# Motor0.net
KiCad netlist of a schematic drawn in Altium Designer
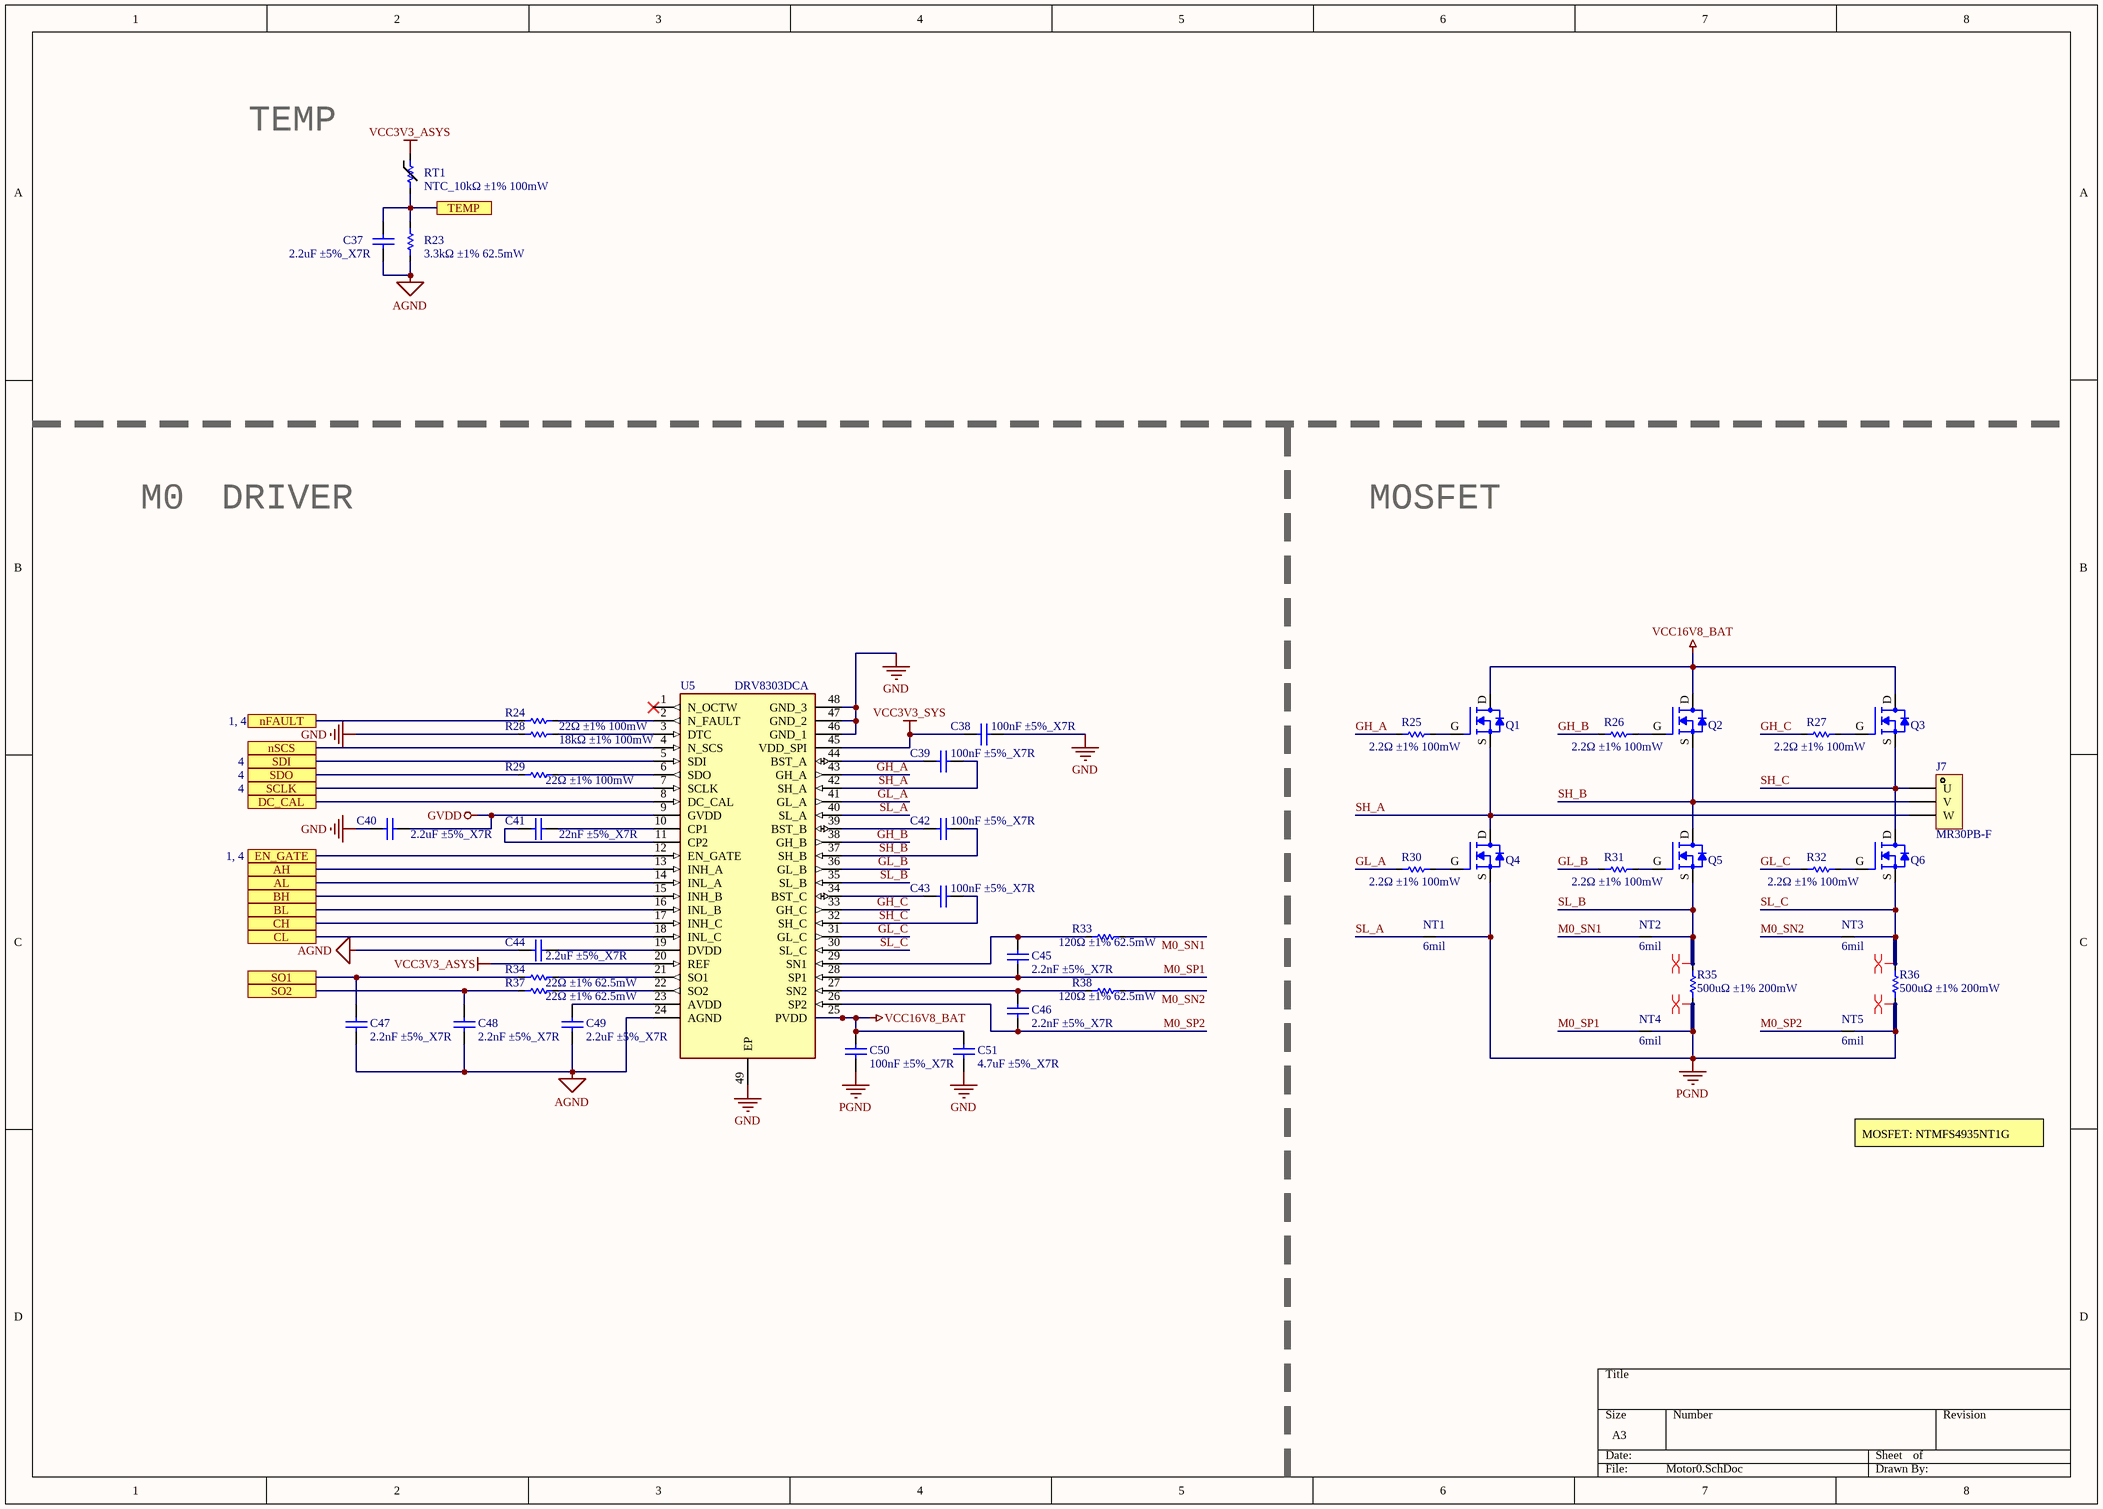
[diagram p0: Motor0.SchDoc]

(export (version "E")
  (design (tool "Eeschema 10.0.6"))
  (components
    (comp (ref "C37")
      (value "2.2uF ±5%_X7R")
      (footprint "C0402")
      (description "Capacitor")
      (fields (field (name "PUBLISHER") "Altium Limited"))
      (libsource (lib "Component") (part "Cap"))
    )
    (comp (ref "C38")
      (value "100nF ±5%_X7R")
      (footprint "C0402")
      (description "Capacitor")
      (fields (field (name "PUBLISHER") "Altium Limited"))
      (libsource (lib "Component") (part "Cap"))
    )
    (comp (ref "C39")
      (value "100nF ±5%_X7R")
      (footprint "C0402")
      (description "Capacitor")
      (fields (field (name "PUBLISHER") "Altium Limited"))
      (libsource (lib "Component") (part "Cap"))
    )
    (comp (ref "C40")
      (value "2.2uF ±5%_X7R")
      (footprint "C0402")
      (description "CL05A225KO5NQNC")
      (fields (field (name "PUBLISHER") "Altium Limited"))
      (libsource (lib "Component") (part "Cap"))
    )
    (comp (ref "C41")
      (value "22nF ±5%_X7R")
      (footprint "C0402")
      (description "Capacitor")
      (fields (field (name "PUBLISHER") "Altium Limited"))
      (libsource (lib "Component") (part "Cap"))
    )
    (comp (ref "C42")
      (value "100nF ±5%_X7R")
      (footprint "C0402")
      (description "Capacitor")
      (fields (field (name "PUBLISHER") "Altium Limited"))
      (libsource (lib "Component") (part "Cap"))
    )
    (comp (ref "C43")
      (value "100nF ±5%_X7R")
      (footprint "C0402")
      (description "Capacitor")
      (fields (field (name "PUBLISHER") "Altium Limited"))
      (libsource (lib "Component") (part "Cap"))
    )
    (comp (ref "C44")
      (value "2.2uF ±5%_X7R")
      (footprint "C0402")
      (description "CL05A225KO5NQNC")
      (fields (field (name "PUBLISHER") "Altium Limited"))
      (libsource (lib "Component") (part "Cap"))
    )
    (comp (ref "C45")
      (value "2.2nF ±5%_X7R")
      (footprint "C0402")
      (description "Capacitor")
      (fields (field (name "PUBLISHER") "Altium Limited"))
      (libsource (lib "Component") (part "Cap"))
    )
    (comp (ref "C46")
      (value "2.2nF ±5%_X7R")
      (footprint "C0402")
      (description "Capacitor")
      (fields (field (name "PUBLISHER") "Altium Limited"))
      (libsource (lib "Component") (part "Cap"))
    )
    (comp (ref "C47")
      (value "2.2nF ±5%_X7R")
      (footprint "C0402")
      (description "Capacitor")
      (fields (field (name "PUBLISHER") "Altium Limited"))
      (libsource (lib "Component") (part "Cap"))
    )
    (comp (ref "C48")
      (value "2.2nF ±5%_X7R")
      (footprint "C0402")
      (description "Capacitor")
      (fields (field (name "PUBLISHER") "Altium Limited"))
      (libsource (lib "Component") (part "Cap"))
    )
    (comp (ref "C49")
      (value "2.2uF ±5%_X7R")
      (footprint "C0402")
      (description "CL05A225KO5NQNC")
      (fields (field (name "PUBLISHER") "Altium Limited"))
      (libsource (lib "Component") (part "Cap"))
    )
    (comp (ref "C50")
      (value "100nF ±5%_X7R")
      (footprint "C0402")
      (description "Capacitor")
      (fields (field (name "PUBLISHER") "Altium Limited"))
      (libsource (lib "Component") (part "Cap"))
    )
    (comp (ref "C51")
      (value "4.7uF ±5%_X7R")
      (footprint "C0603")
      (description "Capacitor")
      (fields (field (name "PUBLISHER") "Altium Limited"))
      (libsource (lib "Component") (part "Cap"))
    )
    (comp (ref "J7")
      (value "MR30PB-F")
      (footprint "MR30PB-F [Straight] [SMT]")
      (description "驱动器端")
      (libsource (lib "Connectivity_Plugs") (part "MR30PB-F [Straight] [SMT]"))
    )
    (comp (ref "NT1") (value "6mil") (footprint "NETTIE_6mil") (libsource (lib "Component") (part "NETTIE")))
    (comp (ref "NT2") (value "6mil") (footprint "NETTIE_6mil") (libsource (lib "Component") (part "NETTIE")))
    (comp (ref "NT3") (value "6mil") (footprint "NETTIE_6mil") (libsource (lib "Component") (part "NETTIE")))
    (comp (ref "NT4") (value "6mil") (footprint "NETTIE_6mil") (libsource (lib "Component") (part "NETTIE")))
    (comp (ref "NT5") (value "6mil") (footprint "NETTIE_6mil") (libsource (lib "Component") (part "NETTIE")))
    (comp (ref "Q1")
      (value "BSC027N04LSG")
      (footprint "NRVTS10100EMFST1G")
      (description "MOSFET – Power, Single,\r\nN-Channel, PG-TDSON-8\r\nSuperSO8 5x6\r\n40 V, 139 A")
      (fields
        (field (name "MANUFACTURER") "ON Semiconductor")
        (field (name "MANUFACTURER PART NUMBER") "NTMFS4935NT1G")
      )
      (libsource (lib "Component") (part "MOSFET-N"))
    )
    (comp (ref "Q2")
      (value "BSC027N04LSG")
      (footprint "NRVTS10100EMFST1G")
      (description "MOSFET – Power, Single,\r\nN-Channel, PG-TDSON-8\r\nSuperSO8 5x6\r\n40 V, 139 A")
      (fields
        (field (name "MANUFACTURER") "ON Semiconductor")
        (field (name "MANUFACTURER PART NUMBER") "NTMFS4935NT1G")
      )
      (libsource (lib "Component") (part "MOSFET-N"))
    )
    (comp (ref "Q3")
      (value "BSC027N04LSG")
      (footprint "NRVTS10100EMFST1G")
      (description "MOSFET – Power, Single,\r\nN-Channel, PG-TDSON-8\r\nSuperSO8 5x6\r\n40 V, 139 A")
      (fields
        (field (name "MANUFACTURER") "ON Semiconductor")
        (field (name "MANUFACTURER PART NUMBER") "NTMFS4935NT1G")
      )
      (libsource (lib "Component") (part "MOSFET-N"))
    )
    (comp (ref "Q4")
      (value "BSC027N04LSG")
      (footprint "NRVTS10100EMFST1G")
      (description "MOSFET – Power, Single,\r\nN-Channel, PG-TDSON-8\r\nSuperSO8 5x6\r\n40 V, 139 A")
      (fields
        (field (name "MANUFACTURER") "ON Semiconductor")
        (field (name "MANUFACTURER PART NUMBER") "NTMFS4935NT1G")
      )
      (libsource (lib "Component") (part "MOSFET-N"))
    )
    (comp (ref "Q5")
      (value "BSC027N04LSG")
      (footprint "NRVTS10100EMFST1G")
      (description "MOSFET – Power, Single,\r\nN-Channel, PG-TDSON-8\r\nSuperSO8 5x6\r\n40 V, 139 A")
      (fields
        (field (name "MANUFACTURER") "ON Semiconductor")
        (field (name "MANUFACTURER PART NUMBER") "NTMFS4935NT1G")
      )
      (libsource (lib "Component") (part "MOSFET-N"))
    )
    (comp (ref "Q6")
      (value "BSC027N04LSG")
      (footprint "NRVTS10100EMFST1G")
      (description "MOSFET – Power, Single,\r\nN-Channel, PG-TDSON-8\r\nSuperSO8 5x6\r\n40 V, 139 A")
      (fields
        (field (name "MANUFACTURER") "ON Semiconductor")
        (field (name "MANUFACTURER PART NUMBER") "NTMFS4935NT1G")
      )
      (libsource (lib "Component") (part "MOSFET-N"))
    )
    (comp (ref "R23")
      (value "3.3kΩ ±1% 62.5mW")
      (footprint "R0402")
      (description "Resistor")
      (fields (field (name "PUBLISHER") "Altium Limited"))
      (libsource (lib "Component") (part "Res"))
    )
    (comp (ref "R24")
      (value "22Ω ±1% 100mW")
      (footprint "R0402")
      (description "Resistor")
      (fields (field (name "PUBLISHER") "Altium Limited"))
      (libsource (lib "Component") (part "Res"))
    )
    (comp (ref "R25")
      (value "2.2Ω ±1% 100mW")
      (footprint "R0402")
      (description "Resistor")
      (fields (field (name "PUBLISHER") "Altium Limited"))
      (libsource (lib "Component") (part "Res"))
    )
    (comp (ref "R26")
      (value "2.2Ω ±1% 100mW")
      (footprint "R0402")
      (description "Resistor")
      (fields (field (name "PUBLISHER") "Altium Limited"))
      (libsource (lib "Component") (part "Res"))
    )
    (comp (ref "R27")
      (value "2.2Ω ±1% 100mW")
      (footprint "R0402")
      (description "Resistor")
      (fields (field (name "PUBLISHER") "Altium Limited"))
      (libsource (lib "Component") (part "Res"))
    )
    (comp (ref "R28")
      (value "18kΩ ±1% 100mW")
      (footprint "R0402")
      (description "Resistor")
      (fields (field (name "PUBLISHER") "Altium Limited"))
      (libsource (lib "Component") (part "Res"))
    )
    (comp (ref "R29")
      (value "22Ω ±1% 100mW")
      (footprint "R0402")
      (description "Resistor")
      (fields (field (name "PUBLISHER") "Altium Limited"))
      (libsource (lib "Component") (part "Res"))
    )
    (comp (ref "R30")
      (value "2.2Ω ±1% 100mW")
      (footprint "R0402")
      (description "Resistor")
      (fields (field (name "PUBLISHER") "Altium Limited"))
      (libsource (lib "Component") (part "Res"))
    )
    (comp (ref "R31")
      (value "2.2Ω ±1% 100mW")
      (footprint "R0402")
      (description "Resistor")
      (fields (field (name "PUBLISHER") "Altium Limited"))
      (libsource (lib "Component") (part "Res"))
    )
    (comp (ref "R32")
      (value "2.2Ω ±1% 100mW")
      (footprint "R0402")
      (description "Resistor")
      (fields (field (name "PUBLISHER") "Altium Limited"))
      (libsource (lib "Component") (part "Res"))
    )
    (comp (ref "R33")
      (value "120Ω ±1% 62.5mW")
      (footprint "R0402")
      (description "Resistor")
      (fields (field (name "PUBLISHER") "Altium Limited"))
      (libsource (lib "Component") (part "Res"))
    )
    (comp (ref "R34")
      (value "22Ω ±1% 62.5mW")
      (footprint "R0402")
      (description "Resistor")
      (fields (field (name "PUBLISHER") "Altium Limited"))
      (libsource (lib "Component") (part "Res"))
    )
    (comp (ref "R35")
      (value "500uΩ ±1% 200mW")
      (footprint "R2512")
      (description "Resistor")
      (fields (field (name "PUBLISHER") "Altium Limited"))
      (libsource (lib "Component") (part "Res"))
    )
    (comp (ref "R36")
      (value "500uΩ ±1% 200mW")
      (footprint "R2512")
      (description "Resistor")
      (fields (field (name "PUBLISHER") "Altium Limited"))
      (libsource (lib "Component") (part "Res"))
    )
    (comp (ref "R37")
      (value "22Ω ±1% 62.5mW")
      (footprint "R0402")
      (description "Resistor")
      (fields (field (name "PUBLISHER") "Altium Limited"))
      (libsource (lib "Component") (part "Res"))
    )
    (comp (ref "R38")
      (value "120Ω ±1% 62.5mW")
      (footprint "R0402")
      (description "Resistor")
      (fields (field (name "PUBLISHER") "Altium Limited"))
      (libsource (lib "Component") (part "Res"))
    )
    (comp (ref "RT1")
      (value "NTC_10kΩ ±1% 100mW")
      (footprint "R0402")
      (description "THERMISTOR 10K OHM NTC 0402 SMD")
      (libsource (lib "Component") (part "TEMP RES"))
    )
    (comp (ref "U5")
      (value "DRV8303DCA")
      (footprint "SamacSys:SOP50P810X120-49N")
      (description "Integrated Circuit")
      (fields (field (name "MOUSER PART NUMBER") "595-DRV8303DCA"))
      (libsource (lib "*") (part "DRV8303DCA"))
    )
  )
  (nets
    (net (code "1") (name "/AH") (class "Default")
      (node (ref "U5") (pin "13") (pinfunction "INH_A_13") (pintype "input"))
    )
    (net (code "2") (name "/AL") (class "Default")
      (node (ref "U5") (pin "14") (pinfunction "INL_A_14") (pintype "input"))
    )
    (net (code "3") (name "/BH") (class "Default")
      (node (ref "U5") (pin "15") (pinfunction "INH_B_15") (pintype "input"))
    )
    (net (code "4") (name "/BL") (class "Default")
      (node (ref "U5") (pin "16") (pinfunction "INL_B_16") (pintype "input"))
    )
    (net (code "5") (name "/CH") (class "Default")
      (node (ref "U5") (pin "17") (pinfunction "INH_C_17") (pintype "input"))
    )
    (net (code "6") (name "/CL") (class "Default")
      (node (ref "U5") (pin "18") (pinfunction "INL_C_18") (pintype "input"))
    )
    (net (code "7") (name "/DC_CAL") (class "Default")
      (node (ref "U5") (pin "8") (pinfunction "DC_CAL_8") (pintype "input"))
    )
    (net (code "8") (name "/EN_GATE") (class "Default")
      (node (ref "U5") (pin "12") (pinfunction "EN_GATE_12") (pintype "input"))
    )
    (net (code "9") (name "/GH_A") (class "Default")
      (node (ref "R25") (pin "1") (pinfunction "1_1") (pintype "passive"))
      (node (ref "U5") (pin "43") (pinfunction "GH_A_43") (pintype "output"))
    )
    (net (code "10") (name "/GH_B") (class "Default")
      (node (ref "R26") (pin "1") (pinfunction "1_1") (pintype "passive"))
      (node (ref "U5") (pin "38") (pinfunction "GH_B_38") (pintype "output"))
    )
    (net (code "11") (name "/GH_C") (class "Default")
      (node (ref "R27") (pin "1") (pinfunction "1_1") (pintype "passive"))
      (node (ref "U5") (pin "33") (pinfunction "GH_C_33") (pintype "output"))
    )
    (net (code "12") (name "/GL_A") (class "Default")
      (node (ref "R30") (pin "1") (pinfunction "1_1") (pintype "passive"))
      (node (ref "U5") (pin "41") (pinfunction "GL_A_41") (pintype "output"))
    )
    (net (code "13") (name "/GL_B") (class "Default")
      (node (ref "R31") (pin "1") (pinfunction "1_1") (pintype "passive"))
      (node (ref "U5") (pin "36") (pinfunction "GL_B_36") (pintype "output"))
    )
    (net (code "14") (name "/GL_C") (class "Default")
      (node (ref "R32") (pin "1") (pinfunction "1_1") (pintype "passive"))
      (node (ref "U5") (pin "31") (pinfunction "GL_C_31") (pintype "output"))
    )
    (net (code "15") (name "/M0_SN1") (class "Default")
      (node (ref "NT2") (pin "1") (pinfunction "1_1") (pintype "passive"))
      (node (ref "R33") (pin "1") (pinfunction "1_1") (pintype "passive"))
    )
    (net (code "16") (name "/M0_SN2") (class "Default")
      (node (ref "NT3") (pin "1") (pinfunction "1_1") (pintype "passive"))
      (node (ref "R38") (pin "1") (pinfunction "1_1") (pintype "passive"))
    )
    (net (code "17") (name "/M0_SP1") (class "Default")
      (node (ref "C45") (pin "1") (pinfunction "1_1") (pintype "passive"))
      (node (ref "NT4") (pin "1") (pinfunction "1_1") (pintype "passive"))
      (node (ref "U5") (pin "28") (pinfunction "SP1_28") (pintype "input"))
    )
    (net (code "18") (name "/M0_SP2") (class "Default")
      (node (ref "C46") (pin "1") (pinfunction "1_1") (pintype "passive"))
      (node (ref "NT5") (pin "1") (pinfunction "1_1") (pintype "passive"))
      (node (ref "U5") (pin "26") (pinfunction "SP2_26") (pintype "input"))
    )
    (net (code "19") (name "/SCLK") (class "Default")
      (node (ref "U5") (pin "7") (pinfunction "SCLK_7") (pintype "input"))
    )
    (net (code "20") (name "/SDI") (class "Default")
      (node (ref "U5") (pin "5") (pinfunction "SDI_5") (pintype "input"))
    )
    (net (code "21") (name "/SDO") (class "Default")
      (node (ref "R29") (pin "1") (pinfunction "1_1") (pintype "passive"))
    )
    (net (code "22") (name "/SH_A") (class "Default")
      (node (ref "C39") (pin "1") (pinfunction "1_1") (pintype "passive"))
      (node (ref "J7") (pin "3") (pinfunction "W_3") (pintype "passive"))
      (node (ref "Q1") (pin "S") (pinfunction "S_S") (pintype "passive"))
      (node (ref "Q4") (pin "D") (pinfunction "D_D") (pintype "passive"))
      (node (ref "U5") (pin "42") (pinfunction "SH_A_42") (pintype "input"))
    )
    (net (code "23") (name "/SH_B") (class "Default")
      (node (ref "C42") (pin "1") (pinfunction "1_1") (pintype "passive"))
      (node (ref "J7") (pin "2") (pinfunction "V_2") (pintype "passive"))
      (node (ref "Q2") (pin "S") (pinfunction "S_S") (pintype "passive"))
      (node (ref "Q5") (pin "D") (pinfunction "D_D") (pintype "passive"))
      (node (ref "U5") (pin "37") (pinfunction "SH_B_37") (pintype "input"))
    )
    (net (code "24") (name "/SH_C") (class "Default")
      (node (ref "C43") (pin "1") (pinfunction "1_1") (pintype "passive"))
      (node (ref "J7") (pin "1") (pinfunction "U_1") (pintype "passive"))
      (node (ref "Q3") (pin "S") (pinfunction "S_S") (pintype "passive"))
      (node (ref "Q6") (pin "D") (pinfunction "D_D") (pintype "passive"))
      (node (ref "U5") (pin "32") (pinfunction "SH_C_32") (pintype "input"))
    )
    (net (code "25") (name "/SL_A") (class "Default")
      (node (ref "NT1") (pin "1") (pinfunction "1_1") (pintype "passive"))
      (node (ref "U5") (pin "40") (pinfunction "SL_A_40") (pintype "input"))
    )
    (net (code "26") (name "/SL_B") (class "Default")
      (node (ref "NT2") (pin "2") (pinfunction "2_2") (pintype "passive"))
      (node (ref "Q5") (pin "S") (pinfunction "S_S") (pintype "passive"))
      (node (ref "R35") (pin "2") (pinfunction "2_2") (pintype "passive"))
      (node (ref "U5") (pin "35") (pinfunction "SL_B_35") (pintype "input"))
    )
    (net (code "27") (name "/SL_C") (class "Default")
      (node (ref "NT3") (pin "2") (pinfunction "2_2") (pintype "passive"))
      (node (ref "Q6") (pin "S") (pinfunction "S_S") (pintype "passive"))
      (node (ref "R36") (pin "2") (pinfunction "2_2") (pintype "passive"))
      (node (ref "U5") (pin "30") (pinfunction "SL_C_30") (pintype "input"))
    )
    (net (code "28") (name "/SO1") (class "Default")
      (node (ref "C47") (pin "2") (pinfunction "2_2") (pintype "passive"))
      (node (ref "R34") (pin "2") (pinfunction "2_2") (pintype "passive"))
    )
    (net (code "29") (name "/SO2") (class "Default")
      (node (ref "C48") (pin "2") (pinfunction "2_2") (pintype "passive"))
      (node (ref "R37") (pin "2") (pinfunction "2_2") (pintype "passive"))
    )
    (net (code "30") (name "/TEMP") (class "Default")
      (node (ref "C37") (pin "2") (pinfunction "2_2") (pintype "passive"))
      (node (ref "R23") (pin "1") (pinfunction "1_1") (pintype "passive"))
      (node (ref "RT1") (pin "2") (pinfunction "2_2") (pintype "passive"))
    )
    (net (code "31") (name "/nFAULT") (class "Default")
      (node (ref "R24") (pin "1") (pinfunction "1_1") (pintype "passive"))
    )
    (net (code "32") (name "/nSCS") (class "Default")
      (node (ref "U5") (pin "4") (pinfunction "N_SCS_4") (pintype "input"))
    )
    (net (code "33") (name "AGND") (class "Default")
      (node (ref "C37") (pin "1") (pinfunction "1_1") (pintype "passive"))
      (node (ref "C44") (pin "2") (pinfunction "2_2") (pintype "passive"))
      (node (ref "C47") (pin "1") (pinfunction "1_1") (pintype "passive"))
      (node (ref "C48") (pin "1") (pinfunction "1_1") (pintype "passive"))
      (node (ref "C49") (pin "1") (pinfunction "1_1") (pintype "passive"))
      (node (ref "R23") (pin "2") (pinfunction "2_2") (pintype "passive"))
      (node (ref "U5") (pin "24") (pinfunction "AGND_24") (pintype "power_in"))
    )
    (net (code "34") (name "GND") (class "Default")
      (node (ref "C38") (pin "1") (pinfunction "1_1") (pintype "passive"))
      (node (ref "C40") (pin "1") (pinfunction "1_1") (pintype "passive"))
      (node (ref "C51") (pin "1") (pinfunction "1_1") (pintype "passive"))
      (node (ref "R28") (pin "2") (pinfunction "2_2") (pintype "passive"))
      (node (ref "U5") (pin "46") (pinfunction "GND_1_46") (pintype "power_in"))
      (node (ref "U5") (pin "47") (pinfunction "GND_2_47") (pintype "power_in"))
      (node (ref "U5") (pin "48") (pinfunction "GND_3_48") (pintype "power_in"))
      (node (ref "U5") (pin "49") (pinfunction "EP_49") (pintype "passive"))
    )
    (net (code "35") (name "GVDD") (class "Default")
      (node (ref "C40") (pin "2") (pinfunction "2_2") (pintype "passive"))
      (node (ref "U5") (pin "9") (pinfunction "GVDD_9") (pintype "power_in"))
    )
    (net (code "36") (name "Net-(Q1-PadG)") (class "Default")
      (node (ref "Q1") (pin "G") (pinfunction "G_G") (pintype "passive"))
      (node (ref "R25") (pin "2") (pinfunction "2_2") (pintype "passive"))
    )
    (net (code "37") (name "Net-(Q2-PadG)") (class "Default")
      (node (ref "Q2") (pin "G") (pinfunction "G_G") (pintype "passive"))
      (node (ref "R26") (pin "2") (pinfunction "2_2") (pintype "passive"))
    )
    (net (code "38") (name "Net-(Q3-PadG)") (class "Default")
      (node (ref "Q3") (pin "G") (pinfunction "G_G") (pintype "passive"))
      (node (ref "R27") (pin "2") (pinfunction "2_2") (pintype "passive"))
    )
    (net (code "39") (name "Net-(Q4-PadG)") (class "Default")
      (node (ref "Q4") (pin "G") (pinfunction "G_G") (pintype "passive"))
      (node (ref "R30") (pin "2") (pinfunction "2_2") (pintype "passive"))
    )
    (net (code "40") (name "Net-(Q5-PadG)") (class "Default")
      (node (ref "Q5") (pin "G") (pinfunction "G_G") (pintype "passive"))
      (node (ref "R31") (pin "2") (pinfunction "2_2") (pintype "passive"))
    )
    (net (code "41") (name "Net-(Q6-PadG)") (class "Default")
      (node (ref "Q6") (pin "G") (pinfunction "G_G") (pintype "passive"))
      (node (ref "R32") (pin "2") (pinfunction "2_2") (pintype "passive"))
    )
    (net (code "42") (name "Net-(U5-AVDD)") (class "Default")
      (node (ref "C49") (pin "2") (pinfunction "2_2") (pintype "passive"))
      (node (ref "U5") (pin "23") (pinfunction "AVDD_23") (pintype "power_in"))
    )
    (net (code "43") (name "Net-(U5-BST_A)") (class "Default")
      (node (ref "C39") (pin "2") (pinfunction "2_2") (pintype "passive"))
      (node (ref "U5") (pin "44") (pinfunction "BST_A_44") (pintype "bidirectional"))
    )
    (net (code "44") (name "Net-(U5-BST_B)") (class "Default")
      (node (ref "C42") (pin "2") (pinfunction "2_2") (pintype "passive"))
      (node (ref "U5") (pin "39") (pinfunction "BST_B_39") (pintype "bidirectional"))
    )
    (net (code "45") (name "Net-(U5-BST_C)") (class "Default")
      (node (ref "C43") (pin "2") (pinfunction "2_2") (pintype "passive"))
      (node (ref "U5") (pin "34") (pinfunction "BST_C_34") (pintype "bidirectional"))
    )
    (net (code "46") (name "Net-(U5-CP1)") (class "Default")
      (node (ref "C41") (pin "1") (pinfunction "1_1") (pintype "passive"))
      (node (ref "U5") (pin "10") (pinfunction "CP1_10") (pintype "power_in"))
    )
    (net (code "47") (name "Net-(U5-CP2)") (class "Default")
      (node (ref "C41") (pin "2") (pinfunction "2_2") (pintype "passive"))
      (node (ref "U5") (pin "11") (pinfunction "CP2_11") (pintype "power_in"))
    )
    (net (code "48") (name "Net-(U5-DTC)") (class "Default")
      (node (ref "R28") (pin "1") (pinfunction "1_1") (pintype "passive"))
      (node (ref "U5") (pin "3") (pinfunction "DTC_3") (pintype "input"))
    )
    (net (code "49") (name "Net-(U5-DVDD)") (class "Default")
      (node (ref "C44") (pin "1") (pinfunction "1_1") (pintype "passive"))
      (node (ref "U5") (pin "19") (pinfunction "DVDD_19") (pintype "power_in"))
    )
    (net (code "50") (name "Net-(U5-N_FAULT)") (class "Default")
      (node (ref "R24") (pin "2") (pinfunction "2_2") (pintype "passive"))
      (node (ref "U5") (pin "2") (pinfunction "N_FAULT_2") (pintype "output"))
    )
    (net (code "51") (name "Net-(U5-SDO)") (class "Default")
      (node (ref "R29") (pin "2") (pinfunction "2_2") (pintype "passive"))
      (node (ref "U5") (pin "6") (pinfunction "SDO_6") (pintype "output"))
    )
    (net (code "52") (name "Net-(U5-SN1)") (class "Default")
      (node (ref "C45") (pin "2") (pinfunction "2_2") (pintype "passive"))
      (node (ref "R33") (pin "2") (pinfunction "2_2") (pintype "passive"))
      (node (ref "U5") (pin "29") (pinfunction "SN1_29") (pintype "input"))
    )
    (net (code "53") (name "Net-(U5-SN2)") (class "Default")
      (node (ref "C46") (pin "2") (pinfunction "2_2") (pintype "passive"))
      (node (ref "R38") (pin "2") (pinfunction "2_2") (pintype "passive"))
      (node (ref "U5") (pin "27") (pinfunction "SN2_27") (pintype "input"))
    )
    (net (code "54") (name "Net-(U5-SO1)") (class "Default")
      (node (ref "R34") (pin "1") (pinfunction "1_1") (pintype "passive"))
      (node (ref "U5") (pin "21") (pinfunction "SO1_21") (pintype "output"))
    )
    (net (code "55") (name "Net-(U5-SO2)") (class "Default")
      (node (ref "R37") (pin "1") (pinfunction "1_1") (pintype "passive"))
      (node (ref "U5") (pin "22") (pinfunction "SO2_22") (pintype "output"))
    )
    (net (code "56") (name "PGND") (class "Default")
      (node (ref "C50") (pin "1") (pinfunction "1_1") (pintype "passive"))
      (node (ref "NT1") (pin "2") (pinfunction "2_2") (pintype "passive"))
      (node (ref "NT4") (pin "2") (pinfunction "2_2") (pintype "passive"))
      (node (ref "NT5") (pin "2") (pinfunction "2_2") (pintype "passive"))
      (node (ref "Q4") (pin "S") (pinfunction "S_S") (pintype "passive"))
      (node (ref "R35") (pin "1") (pinfunction "1_1") (pintype "passive"))
      (node (ref "R36") (pin "1") (pinfunction "1_1") (pintype "passive"))
    )
    (net (code "57") (name "VCC3V3_ASYS") (class "Default")
      (node (ref "RT1") (pin "1") (pinfunction "1_1") (pintype "passive"))
      (node (ref "U5") (pin "20") (pinfunction "REF_20") (pintype "input"))
    )
    (net (code "58") (name "VCC3V3_SYS") (class "Default")
      (node (ref "C38") (pin "2") (pinfunction "2_2") (pintype "passive"))
      (node (ref "U5") (pin "45") (pinfunction "VDD_SPI_45") (pintype "power_in"))
    )
    (net (code "59") (name "VCC16V8_BAT") (class "Default")
      (node (ref "C50") (pin "2") (pinfunction "2_2") (pintype "passive"))
      (node (ref "C51") (pin "2") (pinfunction "2_2") (pintype "passive"))
      (node (ref "Q1") (pin "D") (pinfunction "D_D") (pintype "passive"))
      (node (ref "Q2") (pin "D") (pinfunction "D_D") (pintype "passive"))
      (node (ref "Q3") (pin "D") (pinfunction "D_D") (pintype "passive"))
      (node (ref "U5") (pin "25") (pinfunction "PVDD_25") (pintype "power_in"))
    )
    (net (code "60") (name "unconnected-(U5-N_OCTW-Pad1)") (class "Default")
      (node (ref "U5") (pin "1") (pinfunction "N_OCTW_1") (pintype "output+no_connect"))
    )
  )
)
